# con-top-j3-1.net
KiCad netlist of a schematic drawn in Altium Designer
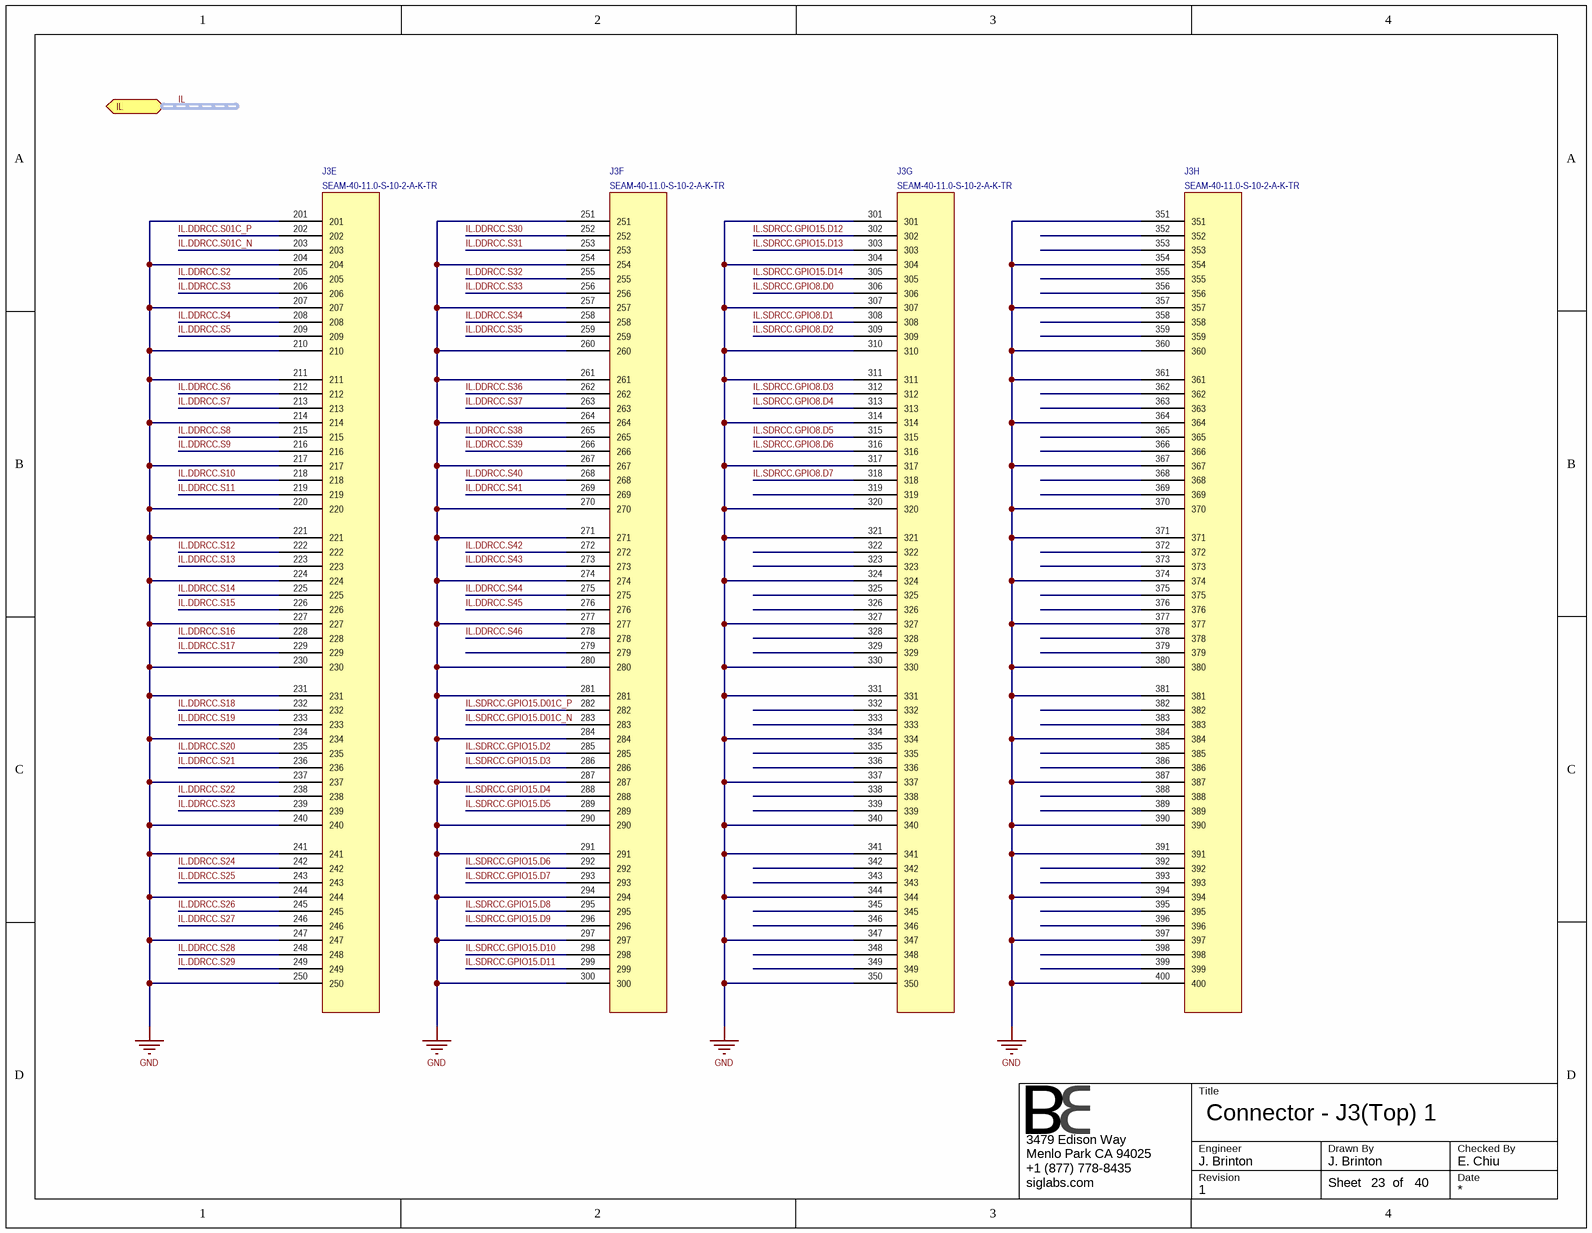
[diagram p0: con-top-j3-1.SchDoc]

(export (version "E")
  (design (tool "Eeschema 10.0.6"))
  (components
    (comp (ref "J3")
      (value "SEAM-40-11.0-S-10-2-A-K-TR")
      (footprint "samtec:SEAM-40-11.0-S-10-2-A-K-TR")
      (description "Terminal Array Assembly, Surface Mount, 0.050\" Pitch, 400 Pins")
      (fields (field (name "MANUFACTURER") "Samtec"))
      (libsource (lib "samtec") (part "SEAM-40-11.0-S-10-2-A-K-TR"))
    )
  )
  (nets
    (net (code "2") (name "/IL.DDRCC.S01C_N") (class "Default")
      (node (ref "J3") (pin "203") (pinfunction "203_203") (pintype "passive"))
    )
    (net (code "3") (name "/IL.DDRCC.S01C_P") (class "Default")
      (node (ref "J3") (pin "202") (pinfunction "202_202") (pintype "passive"))
    )
    (net (code "4") (name "/IL.DDRCC.S2") (class "Default")
      (node (ref "J3") (pin "205") (pinfunction "205_205") (pintype "passive"))
    )
    (net (code "5") (name "/IL.DDRCC.S3") (class "Default")
      (node (ref "J3") (pin "206") (pinfunction "206_206") (pintype "passive"))
    )
    (net (code "6") (name "/IL.DDRCC.S4") (class "Default")
      (node (ref "J3") (pin "208") (pinfunction "208_208") (pintype "passive"))
    )
    (net (code "7") (name "/IL.DDRCC.S5") (class "Default")
      (node (ref "J3") (pin "209") (pinfunction "209_209") (pintype "passive"))
    )
    (net (code "8") (name "/IL.DDRCC.S6") (class "Default")
      (node (ref "J3") (pin "212") (pinfunction "212_212") (pintype "passive"))
    )
    (net (code "9") (name "/IL.DDRCC.S7") (class "Default")
      (node (ref "J3") (pin "213") (pinfunction "213_213") (pintype "passive"))
    )
    (net (code "10") (name "/IL.DDRCC.S8") (class "Default")
      (node (ref "J3") (pin "215") (pinfunction "215_215") (pintype "passive"))
    )
    (net (code "11") (name "/IL.DDRCC.S9") (class "Default")
      (node (ref "J3") (pin "216") (pinfunction "216_216") (pintype "passive"))
    )
    (net (code "12") (name "/IL.DDRCC.S10") (class "Default")
      (node (ref "J3") (pin "218") (pinfunction "218_218") (pintype "passive"))
    )
    (net (code "13") (name "/IL.DDRCC.S11") (class "Default")
      (node (ref "J3") (pin "219") (pinfunction "219_219") (pintype "passive"))
    )
    (net (code "14") (name "/IL.DDRCC.S12") (class "Default")
      (node (ref "J3") (pin "222") (pinfunction "222_222") (pintype "passive"))
    )
    (net (code "15") (name "/IL.DDRCC.S13") (class "Default")
      (node (ref "J3") (pin "223") (pinfunction "223_223") (pintype "passive"))
    )
    (net (code "16") (name "/IL.DDRCC.S14") (class "Default")
      (node (ref "J3") (pin "225") (pinfunction "225_225") (pintype "passive"))
    )
    (net (code "17") (name "/IL.DDRCC.S15") (class "Default")
      (node (ref "J3") (pin "226") (pinfunction "226_226") (pintype "passive"))
    )
    (net (code "18") (name "/IL.DDRCC.S16") (class "Default")
      (node (ref "J3") (pin "228") (pinfunction "228_228") (pintype "passive"))
    )
    (net (code "19") (name "/IL.DDRCC.S17") (class "Default")
      (node (ref "J3") (pin "229") (pinfunction "229_229") (pintype "passive"))
    )
    (net (code "20") (name "/IL.DDRCC.S18") (class "Default")
      (node (ref "J3") (pin "232") (pinfunction "232_232") (pintype "passive"))
    )
    (net (code "21") (name "/IL.DDRCC.S19") (class "Default")
      (node (ref "J3") (pin "233") (pinfunction "233_233") (pintype "passive"))
    )
    (net (code "22") (name "/IL.DDRCC.S20") (class "Default")
      (node (ref "J3") (pin "235") (pinfunction "235_235") (pintype "passive"))
    )
    (net (code "23") (name "/IL.DDRCC.S21") (class "Default")
      (node (ref "J3") (pin "236") (pinfunction "236_236") (pintype "passive"))
    )
    (net (code "24") (name "/IL.DDRCC.S22") (class "Default")
      (node (ref "J3") (pin "238") (pinfunction "238_238") (pintype "passive"))
    )
    (net (code "25") (name "/IL.DDRCC.S23") (class "Default")
      (node (ref "J3") (pin "239") (pinfunction "239_239") (pintype "passive"))
    )
    (net (code "26") (name "/IL.DDRCC.S24") (class "Default")
      (node (ref "J3") (pin "242") (pinfunction "242_242") (pintype "passive"))
    )
    (net (code "27") (name "/IL.DDRCC.S25") (class "Default")
      (node (ref "J3") (pin "243") (pinfunction "243_243") (pintype "passive"))
    )
    (net (code "28") (name "/IL.DDRCC.S26") (class "Default")
      (node (ref "J3") (pin "245") (pinfunction "245_245") (pintype "passive"))
    )
    (net (code "29") (name "/IL.DDRCC.S27") (class "Default")
      (node (ref "J3") (pin "246") (pinfunction "246_246") (pintype "passive"))
    )
    (net (code "30") (name "/IL.DDRCC.S28") (class "Default")
      (node (ref "J3") (pin "248") (pinfunction "248_248") (pintype "passive"))
    )
    (net (code "31") (name "/IL.DDRCC.S29") (class "Default")
      (node (ref "J3") (pin "249") (pinfunction "249_249") (pintype "passive"))
    )
    (net (code "32") (name "/IL.DDRCC.S30") (class "Default")
      (node (ref "J3") (pin "252") (pinfunction "252_252") (pintype "passive"))
    )
    (net (code "33") (name "/IL.DDRCC.S31") (class "Default")
      (node (ref "J3") (pin "253") (pinfunction "253_253") (pintype "passive"))
    )
    (net (code "34") (name "/IL.DDRCC.S32") (class "Default")
      (node (ref "J3") (pin "255") (pinfunction "255_255") (pintype "passive"))
    )
    (net (code "35") (name "/IL.DDRCC.S33") (class "Default")
      (node (ref "J3") (pin "256") (pinfunction "256_256") (pintype "passive"))
    )
    (net (code "36") (name "/IL.DDRCC.S34") (class "Default")
      (node (ref "J3") (pin "258") (pinfunction "258_258") (pintype "passive"))
    )
    (net (code "37") (name "/IL.DDRCC.S35") (class "Default")
      (node (ref "J3") (pin "259") (pinfunction "259_259") (pintype "passive"))
    )
    (net (code "38") (name "/IL.DDRCC.S36") (class "Default")
      (node (ref "J3") (pin "262") (pinfunction "262_262") (pintype "passive"))
    )
    (net (code "39") (name "/IL.DDRCC.S37") (class "Default")
      (node (ref "J3") (pin "263") (pinfunction "263_263") (pintype "passive"))
    )
    (net (code "40") (name "/IL.DDRCC.S38") (class "Default")
      (node (ref "J3") (pin "265") (pinfunction "265_265") (pintype "passive"))
    )
    (net (code "41") (name "/IL.DDRCC.S39") (class "Default")
      (node (ref "J3") (pin "266") (pinfunction "266_266") (pintype "passive"))
    )
    (net (code "42") (name "/IL.DDRCC.S40") (class "Default")
      (node (ref "J3") (pin "268") (pinfunction "268_268") (pintype "passive"))
    )
    (net (code "43") (name "/IL.DDRCC.S41") (class "Default")
      (node (ref "J3") (pin "269") (pinfunction "269_269") (pintype "passive"))
    )
    (net (code "44") (name "/IL.DDRCC.S42") (class "Default")
      (node (ref "J3") (pin "272") (pinfunction "272_272") (pintype "passive"))
    )
    (net (code "45") (name "/IL.DDRCC.S43") (class "Default")
      (node (ref "J3") (pin "273") (pinfunction "273_273") (pintype "passive"))
    )
    (net (code "46") (name "/IL.DDRCC.S44") (class "Default")
      (node (ref "J3") (pin "275") (pinfunction "275_275") (pintype "passive"))
    )
    (net (code "47") (name "/IL.DDRCC.S45") (class "Default")
      (node (ref "J3") (pin "276") (pinfunction "276_276") (pintype "passive"))
    )
    (net (code "48") (name "/IL.DDRCC.S46") (class "Default")
      (node (ref "J3") (pin "278") (pinfunction "278_278") (pintype "passive"))
    )
    (net (code "49") (name "/IL.SDRCC.GPIO8.D0") (class "Default")
      (node (ref "J3") (pin "306") (pinfunction "306_306") (pintype "passive"))
    )
    (net (code "50") (name "/IL.SDRCC.GPIO8.D1") (class "Default")
      (node (ref "J3") (pin "308") (pinfunction "308_308") (pintype "passive"))
    )
    (net (code "51") (name "/IL.SDRCC.GPIO8.D2") (class "Default")
      (node (ref "J3") (pin "309") (pinfunction "309_309") (pintype "passive"))
    )
    (net (code "52") (name "/IL.SDRCC.GPIO8.D3") (class "Default")
      (node (ref "J3") (pin "312") (pinfunction "312_312") (pintype "passive"))
    )
    (net (code "53") (name "/IL.SDRCC.GPIO8.D4") (class "Default")
      (node (ref "J3") (pin "313") (pinfunction "313_313") (pintype "passive"))
    )
    (net (code "54") (name "/IL.SDRCC.GPIO8.D5") (class "Default")
      (node (ref "J3") (pin "315") (pinfunction "315_315") (pintype "passive"))
    )
    (net (code "55") (name "/IL.SDRCC.GPIO8.D6") (class "Default")
      (node (ref "J3") (pin "316") (pinfunction "316_316") (pintype "passive"))
    )
    (net (code "56") (name "/IL.SDRCC.GPIO8.D7") (class "Default")
      (node (ref "J3") (pin "318") (pinfunction "318_318") (pintype "passive"))
    )
    (net (code "57") (name "/IL.SDRCC.GPIO15.D01C_N") (class "Default")
      (node (ref "J3") (pin "283") (pinfunction "283_283") (pintype "passive"))
    )
    (net (code "58") (name "/IL.SDRCC.GPIO15.D01C_P") (class "Default")
      (node (ref "J3") (pin "282") (pinfunction "282_282") (pintype "passive"))
    )
    (net (code "59") (name "/IL.SDRCC.GPIO15.D2") (class "Default")
      (node (ref "J3") (pin "285") (pinfunction "285_285") (pintype "passive"))
    )
    (net (code "60") (name "/IL.SDRCC.GPIO15.D3") (class "Default")
      (node (ref "J3") (pin "286") (pinfunction "286_286") (pintype "passive"))
    )
    (net (code "61") (name "/IL.SDRCC.GPIO15.D4") (class "Default")
      (node (ref "J3") (pin "288") (pinfunction "288_288") (pintype "passive"))
    )
    (net (code "62") (name "/IL.SDRCC.GPIO15.D5") (class "Default")
      (node (ref "J3") (pin "289") (pinfunction "289_289") (pintype "passive"))
    )
    (net (code "63") (name "/IL.SDRCC.GPIO15.D6") (class "Default")
      (node (ref "J3") (pin "292") (pinfunction "292_292") (pintype "passive"))
    )
    (net (code "64") (name "/IL.SDRCC.GPIO15.D7") (class "Default")
      (node (ref "J3") (pin "293") (pinfunction "293_293") (pintype "passive"))
    )
    (net (code "65") (name "/IL.SDRCC.GPIO15.D8") (class "Default")
      (node (ref "J3") (pin "295") (pinfunction "295_295") (pintype "passive"))
    )
    (net (code "66") (name "/IL.SDRCC.GPIO15.D9") (class "Default")
      (node (ref "J3") (pin "296") (pinfunction "296_296") (pintype "passive"))
    )
    (net (code "67") (name "/IL.SDRCC.GPIO15.D10") (class "Default")
      (node (ref "J3") (pin "298") (pinfunction "298_298") (pintype "passive"))
    )
    (net (code "68") (name "/IL.SDRCC.GPIO15.D11") (class "Default")
      (node (ref "J3") (pin "299") (pinfunction "299_299") (pintype "passive"))
    )
    (net (code "69") (name "/IL.SDRCC.GPIO15.D12") (class "Default")
      (node (ref "J3") (pin "302") (pinfunction "302_302") (pintype "passive"))
    )
    (net (code "70") (name "/IL.SDRCC.GPIO15.D13") (class "Default")
      (node (ref "J3") (pin "303") (pinfunction "303_303") (pintype "passive"))
    )
    (net (code "71") (name "/IL.SDRCC.GPIO15.D14") (class "Default")
      (node (ref "J3") (pin "305") (pinfunction "305_305") (pintype "passive"))
    )
    (net (code "73") (name "GND") (class "Default")
      (node (ref "J3") (pin "201") (pinfunction "201_201") (pintype "passive"))
      (node (ref "J3") (pin "204") (pinfunction "204_204") (pintype "passive"))
      (node (ref "J3") (pin "207") (pinfunction "207_207") (pintype "passive"))
      (node (ref "J3") (pin "210") (pinfunction "210_210") (pintype "passive"))
      (node (ref "J3") (pin "211") (pinfunction "211_211") (pintype "passive"))
      (node (ref "J3") (pin "214") (pinfunction "214_214") (pintype "passive"))
      (node (ref "J3") (pin "217") (pinfunction "217_217") (pintype "passive"))
      (node (ref "J3") (pin "220") (pinfunction "220_220") (pintype "passive"))
      (node (ref "J3") (pin "221") (pinfunction "221_221") (pintype "passive"))
      (node (ref "J3") (pin "224") (pinfunction "224_224") (pintype "passive"))
      (node (ref "J3") (pin "227") (pinfunction "227_227") (pintype "passive"))
      (node (ref "J3") (pin "230") (pinfunction "230_230") (pintype "passive"))
      (node (ref "J3") (pin "231") (pinfunction "231_231") (pintype "passive"))
      (node (ref "J3") (pin "234") (pinfunction "234_234") (pintype "passive"))
      (node (ref "J3") (pin "237") (pinfunction "237_237") (pintype "passive"))
      (node (ref "J3") (pin "240") (pinfunction "240_240") (pintype "passive"))
      (node (ref "J3") (pin "241") (pinfunction "241_241") (pintype "passive"))
      (node (ref "J3") (pin "244") (pinfunction "244_244") (pintype "passive"))
      (node (ref "J3") (pin "247") (pinfunction "247_247") (pintype "passive"))
      (node (ref "J3") (pin "250") (pinfunction "250_250") (pintype "passive"))
      (node (ref "J3") (pin "251") (pinfunction "251_251") (pintype "passive"))
      (node (ref "J3") (pin "254") (pinfunction "254_254") (pintype "passive"))
      (node (ref "J3") (pin "257") (pinfunction "257_257") (pintype "passive"))
      (node (ref "J3") (pin "260") (pinfunction "260_260") (pintype "passive"))
      (node (ref "J3") (pin "261") (pinfunction "261_261") (pintype "passive"))
      (node (ref "J3") (pin "264") (pinfunction "264_264") (pintype "passive"))
      (node (ref "J3") (pin "267") (pinfunction "267_267") (pintype "passive"))
      (node (ref "J3") (pin "270") (pinfunction "270_270") (pintype "passive"))
      (node (ref "J3") (pin "271") (pinfunction "271_271") (pintype "passive"))
      (node (ref "J3") (pin "274") (pinfunction "274_274") (pintype "passive"))
      (node (ref "J3") (pin "277") (pinfunction "277_277") (pintype "passive"))
      (node (ref "J3") (pin "280") (pinfunction "280_280") (pintype "passive"))
      (node (ref "J3") (pin "281") (pinfunction "281_281") (pintype "passive"))
      (node (ref "J3") (pin "284") (pinfunction "284_284") (pintype "passive"))
      (node (ref "J3") (pin "287") (pinfunction "287_287") (pintype "passive"))
      (node (ref "J3") (pin "290") (pinfunction "290_290") (pintype "passive"))
      (node (ref "J3") (pin "291") (pinfunction "291_291") (pintype "passive"))
      (node (ref "J3") (pin "294") (pinfunction "294_294") (pintype "passive"))
      (node (ref "J3") (pin "297") (pinfunction "297_297") (pintype "passive"))
      (node (ref "J3") (pin "300") (pinfunction "300_300") (pintype "passive"))
      (node (ref "J3") (pin "301") (pinfunction "301_301") (pintype "passive"))
      (node (ref "J3") (pin "304") (pinfunction "304_304") (pintype "passive"))
      (node (ref "J3") (pin "307") (pinfunction "307_307") (pintype "passive"))
      (node (ref "J3") (pin "310") (pinfunction "310_310") (pintype "passive"))
      (node (ref "J3") (pin "311") (pinfunction "311_311") (pintype "passive"))
      (node (ref "J3") (pin "314") (pinfunction "314_314") (pintype "passive"))
      (node (ref "J3") (pin "317") (pinfunction "317_317") (pintype "passive"))
      (node (ref "J3") (pin "320") (pinfunction "320_320") (pintype "passive"))
      (node (ref "J3") (pin "321") (pinfunction "321_321") (pintype "passive"))
      (node (ref "J3") (pin "324") (pinfunction "324_324") (pintype "passive"))
      (node (ref "J3") (pin "327") (pinfunction "327_327") (pintype "passive"))
      (node (ref "J3") (pin "330") (pinfunction "330_330") (pintype "passive"))
      (node (ref "J3") (pin "331") (pinfunction "331_331") (pintype "passive"))
      (node (ref "J3") (pin "334") (pinfunction "334_334") (pintype "passive"))
      (node (ref "J3") (pin "337") (pinfunction "337_337") (pintype "passive"))
      (node (ref "J3") (pin "340") (pinfunction "340_340") (pintype "passive"))
      (node (ref "J3") (pin "341") (pinfunction "341_341") (pintype "passive"))
      (node (ref "J3") (pin "344") (pinfunction "344_344") (pintype "passive"))
      (node (ref "J3") (pin "347") (pinfunction "347_347") (pintype "passive"))
      (node (ref "J3") (pin "350") (pinfunction "350_350") (pintype "passive"))
      (node (ref "J3") (pin "351") (pinfunction "351_351") (pintype "passive"))
      (node (ref "J3") (pin "354") (pinfunction "354_354") (pintype "passive"))
      (node (ref "J3") (pin "357") (pinfunction "357_357") (pintype "passive"))
      (node (ref "J3") (pin "360") (pinfunction "360_360") (pintype "passive"))
      (node (ref "J3") (pin "361") (pinfunction "361_361") (pintype "passive"))
      (node (ref "J3") (pin "364") (pinfunction "364_364") (pintype "passive"))
      (node (ref "J3") (pin "367") (pinfunction "367_367") (pintype "passive"))
      (node (ref "J3") (pin "370") (pinfunction "370_370") (pintype "passive"))
      (node (ref "J3") (pin "371") (pinfunction "371_371") (pintype "passive"))
      (node (ref "J3") (pin "374") (pinfunction "374_374") (pintype "passive"))
      (node (ref "J3") (pin "377") (pinfunction "377_377") (pintype "passive"))
      (node (ref "J3") (pin "380") (pinfunction "380_380") (pintype "passive"))
      (node (ref "J3") (pin "381") (pinfunction "381_381") (pintype "passive"))
      (node (ref "J3") (pin "384") (pinfunction "384_384") (pintype "passive"))
      (node (ref "J3") (pin "387") (pinfunction "387_387") (pintype "passive"))
      (node (ref "J3") (pin "390") (pinfunction "390_390") (pintype "passive"))
      (node (ref "J3") (pin "391") (pinfunction "391_391") (pintype "passive"))
      (node (ref "J3") (pin "394") (pinfunction "394_394") (pintype "passive"))
      (node (ref "J3") (pin "397") (pinfunction "397_397") (pintype "passive"))
      (node (ref "J3") (pin "400") (pinfunction "400_400") (pintype "passive"))
    )
    (net (code "74") (name "unconnected-(J3-Pad279)") (class "Default")
      (node (ref "J3") (pin "279") (pinfunction "279_279") (pintype "passive"))
    )
    (net (code "75") (name "unconnected-(J3-Pad319)") (class "Default")
      (node (ref "J3") (pin "319") (pinfunction "319_319") (pintype "passive"))
    )
    (net (code "76") (name "unconnected-(J3-Pad322)") (class "Default")
      (node (ref "J3") (pin "322") (pinfunction "322_322") (pintype "passive"))
    )
    (net (code "77") (name "unconnected-(J3-Pad323)") (class "Default")
      (node (ref "J3") (pin "323") (pinfunction "323_323") (pintype "passive"))
    )
    (net (code "78") (name "unconnected-(J3-Pad325)") (class "Default")
      (node (ref "J3") (pin "325") (pinfunction "325_325") (pintype "passive"))
    )
    (net (code "79") (name "unconnected-(J3-Pad326)") (class "Default")
      (node (ref "J3") (pin "326") (pinfunction "326_326") (pintype "passive"))
    )
    (net (code "80") (name "unconnected-(J3-Pad328)") (class "Default")
      (node (ref "J3") (pin "328") (pinfunction "328_328") (pintype "passive"))
    )
    (net (code "81") (name "unconnected-(J3-Pad329)") (class "Default")
      (node (ref "J3") (pin "329") (pinfunction "329_329") (pintype "passive"))
    )
    (net (code "82") (name "unconnected-(J3-Pad332)") (class "Default")
      (node (ref "J3") (pin "332") (pinfunction "332_332") (pintype "passive"))
    )
    (net (code "83") (name "unconnected-(J3-Pad333)") (class "Default")
      (node (ref "J3") (pin "333") (pinfunction "333_333") (pintype "passive"))
    )
    (net (code "84") (name "unconnected-(J3-Pad335)") (class "Default")
      (node (ref "J3") (pin "335") (pinfunction "335_335") (pintype "passive"))
    )
    (net (code "85") (name "unconnected-(J3-Pad336)") (class "Default")
      (node (ref "J3") (pin "336") (pinfunction "336_336") (pintype "passive"))
    )
    (net (code "86") (name "unconnected-(J3-Pad338)") (class "Default")
      (node (ref "J3") (pin "338") (pinfunction "338_338") (pintype "passive"))
    )
    (net (code "87") (name "unconnected-(J3-Pad339)") (class "Default")
      (node (ref "J3") (pin "339") (pinfunction "339_339") (pintype "passive"))
    )
    (net (code "88") (name "unconnected-(J3-Pad342)") (class "Default")
      (node (ref "J3") (pin "342") (pinfunction "342_342") (pintype "passive"))
    )
    (net (code "89") (name "unconnected-(J3-Pad343)") (class "Default")
      (node (ref "J3") (pin "343") (pinfunction "343_343") (pintype "passive"))
    )
    (net (code "90") (name "unconnected-(J3-Pad345)") (class "Default")
      (node (ref "J3") (pin "345") (pinfunction "345_345") (pintype "passive"))
    )
    (net (code "91") (name "unconnected-(J3-Pad346)") (class "Default")
      (node (ref "J3") (pin "346") (pinfunction "346_346") (pintype "passive"))
    )
    (net (code "92") (name "unconnected-(J3-Pad348)") (class "Default")
      (node (ref "J3") (pin "348") (pinfunction "348_348") (pintype "passive"))
    )
    (net (code "93") (name "unconnected-(J3-Pad349)") (class "Default")
      (node (ref "J3") (pin "349") (pinfunction "349_349") (pintype "passive"))
    )
    (net (code "94") (name "unconnected-(J3-Pad352)") (class "Default")
      (node (ref "J3") (pin "352") (pinfunction "352_352") (pintype "passive"))
    )
    (net (code "95") (name "unconnected-(J3-Pad353)") (class "Default")
      (node (ref "J3") (pin "353") (pinfunction "353_353") (pintype "passive"))
    )
    (net (code "96") (name "unconnected-(J3-Pad355)") (class "Default")
      (node (ref "J3") (pin "355") (pinfunction "355_355") (pintype "passive"))
    )
    (net (code "97") (name "unconnected-(J3-Pad356)") (class "Default")
      (node (ref "J3") (pin "356") (pinfunction "356_356") (pintype "passive"))
    )
    (net (code "98") (name "unconnected-(J3-Pad358)") (class "Default")
      (node (ref "J3") (pin "358") (pinfunction "358_358") (pintype "passive"))
    )
    (net (code "99") (name "unconnected-(J3-Pad359)") (class "Default")
      (node (ref "J3") (pin "359") (pinfunction "359_359") (pintype "passive"))
    )
    (net (code "100") (name "unconnected-(J3-Pad362)") (class "Default")
      (node (ref "J3") (pin "362") (pinfunction "362_362") (pintype "passive"))
    )
    (net (code "101") (name "unconnected-(J3-Pad363)") (class "Default")
      (node (ref "J3") (pin "363") (pinfunction "363_363") (pintype "passive"))
    )
    (net (code "102") (name "unconnected-(J3-Pad365)") (class "Default")
      (node (ref "J3") (pin "365") (pinfunction "365_365") (pintype "passive"))
    )
    (net (code "103") (name "unconnected-(J3-Pad366)") (class "Default")
      (node (ref "J3") (pin "366") (pinfunction "366_366") (pintype "passive"))
    )
    (net (code "104") (name "unconnected-(J3-Pad368)") (class "Default")
      (node (ref "J3") (pin "368") (pinfunction "368_368") (pintype "passive"))
    )
    (net (code "105") (name "unconnected-(J3-Pad369)") (class "Default")
      (node (ref "J3") (pin "369") (pinfunction "369_369") (pintype "passive"))
    )
    (net (code "106") (name "unconnected-(J3-Pad372)") (class "Default")
      (node (ref "J3") (pin "372") (pinfunction "372_372") (pintype "passive"))
    )
    (net (code "107") (name "unconnected-(J3-Pad373)") (class "Default")
      (node (ref "J3") (pin "373") (pinfunction "373_373") (pintype "passive"))
    )
    (net (code "108") (name "unconnected-(J3-Pad375)") (class "Default")
      (node (ref "J3") (pin "375") (pinfunction "375_375") (pintype "passive"))
    )
    (net (code "109") (name "unconnected-(J3-Pad376)") (class "Default")
      (node (ref "J3") (pin "376") (pinfunction "376_376") (pintype "passive"))
    )
    (net (code "110") (name "unconnected-(J3-Pad378)") (class "Default")
      (node (ref "J3") (pin "378") (pinfunction "378_378") (pintype "passive"))
    )
    (net (code "111") (name "unconnected-(J3-Pad379)") (class "Default")
      (node (ref "J3") (pin "379") (pinfunction "379_379") (pintype "passive"))
    )
    (net (code "112") (name "unconnected-(J3-Pad382)") (class "Default")
      (node (ref "J3") (pin "382") (pinfunction "382_382") (pintype "passive"))
    )
    (net (code "113") (name "unconnected-(J3-Pad383)") (class "Default")
      (node (ref "J3") (pin "383") (pinfunction "383_383") (pintype "passive"))
    )
    (net (code "114") (name "unconnected-(J3-Pad385)") (class "Default")
      (node (ref "J3") (pin "385") (pinfunction "385_385") (pintype "passive"))
    )
    (net (code "115") (name "unconnected-(J3-Pad386)") (class "Default")
      (node (ref "J3") (pin "386") (pinfunction "386_386") (pintype "passive"))
    )
    (net (code "116") (name "unconnected-(J3-Pad388)") (class "Default")
      (node (ref "J3") (pin "388") (pinfunction "388_388") (pintype "passive"))
    )
    (net (code "117") (name "unconnected-(J3-Pad389)") (class "Default")
      (node (ref "J3") (pin "389") (pinfunction "389_389") (pintype "passive"))
    )
    (net (code "118") (name "unconnected-(J3-Pad392)") (class "Default")
      (node (ref "J3") (pin "392") (pinfunction "392_392") (pintype "passive"))
    )
    (net (code "119") (name "unconnected-(J3-Pad393)") (class "Default")
      (node (ref "J3") (pin "393") (pinfunction "393_393") (pintype "passive"))
    )
    (net (code "120") (name "unconnected-(J3-Pad395)") (class "Default")
      (node (ref "J3") (pin "395") (pinfunction "395_395") (pintype "passive"))
    )
    (net (code "121") (name "unconnected-(J3-Pad396)") (class "Default")
      (node (ref "J3") (pin "396") (pinfunction "396_396") (pintype "passive"))
    )
    (net (code "122") (name "unconnected-(J3-Pad398)") (class "Default")
      (node (ref "J3") (pin "398") (pinfunction "398_398") (pintype "passive"))
    )
    (net (code "123") (name "unconnected-(J3-Pad399)") (class "Default")
      (node (ref "J3") (pin "399") (pinfunction "399_399") (pintype "passive"))
    )
  )
)
